# LTC2325.net
KiCad netlist of a schematic drawn in Altium Designer
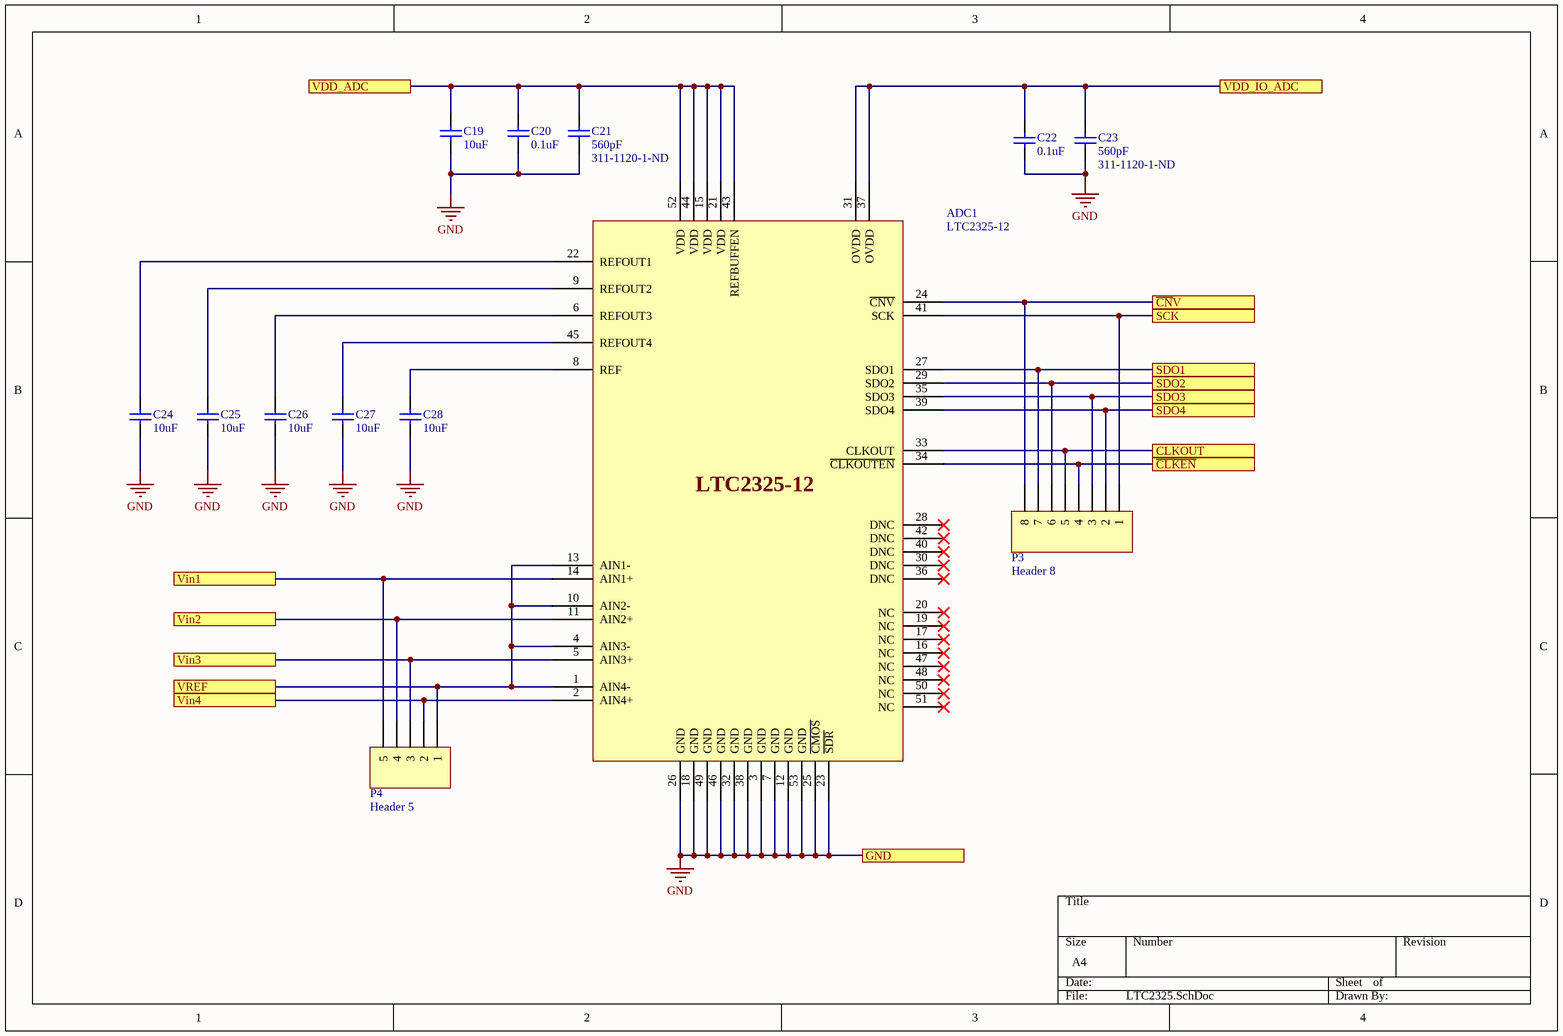
[diagram p0: LTC2325.SchDoc]

(export (version "E")
  (design (tool "Eeschema 10.0.6"))
  (components
    (comp (ref "ADC1")
      (value "LTC2325-12")
      (footprint "LTC2320HUKG")
      (description "Quad, 12-Bit, 5Msps/Ch Simultaneous Sampling ADC")
      (libsource (lib "Chip1_TestBoard") (part "LTC2325-12"))
    )
    (comp (ref "C19")
      (value "10uF")
      (footprint "CLS_Library:C0805")
      (description "Cap 10uF")
      (fields
        (field (name "MANUFACTURER") "Taiyo Yuden")
        (field (name "MANUFACTURER PART NUMBER") "UMK212SD103KD-T")
      )
      (libsource (lib "Chip1_TestBoard") (part "Cap 10uF"))
    )
    (comp (ref "C20")
      (value "0.1uF")
      (footprint "CLS_Library:C0805")
      (description "Cap 0.1uF")
      (fields
        (field (name "MANUFACTURER") "Taiyo Yuden")
        (field (name "MANUFACTURER PART NUMBER") "UMK212SD103KD-T")
      )
      (libsource (lib "Chip1_TestBoard") (part "Cap 0.1uF"))
    )
    (comp (ref "C21")
      (value "560pF")
      (footprint "CLS_Library:C0805")
      (description "Cap 560pF")
      (fields
        (field (name "MANUFACTURER") "Taiyo Yuden")
        (field (name "MANUFACTURER PART NUMBER") "UMK212SD103KD-T")
        (field (name "SUPPLIER PART NUMBER 1") "311-1120-1-ND")
      )
      (libsource (lib "Chip1_TestBoard") (part "Cap 560pF"))
    )
    (comp (ref "C22")
      (value "0.1uF")
      (footprint "CLS_Library:C0805")
      (description "Cap 0.1uF")
      (fields
        (field (name "MANUFACTURER") "Taiyo Yuden")
        (field (name "MANUFACTURER PART NUMBER") "UMK212SD103KD-T")
      )
      (libsource (lib "Chip1_TestBoard") (part "Cap 0.1uF"))
    )
    (comp (ref "C23")
      (value "560pF")
      (footprint "CLS_Library:C0805")
      (description "Cap 560pF")
      (fields
        (field (name "MANUFACTURER") "Taiyo Yuden")
        (field (name "MANUFACTURER PART NUMBER") "UMK212SD103KD-T")
        (field (name "SUPPLIER PART NUMBER 1") "311-1120-1-ND")
      )
      (libsource (lib "Chip1_TestBoard") (part "Cap 560pF"))
    )
    (comp (ref "C24")
      (value "10uF")
      (footprint "CLS_Library:C0805")
      (description "Cap 10uF")
      (fields
        (field (name "MANUFACTURER") "Taiyo Yuden")
        (field (name "MANUFACTURER PART NUMBER") "UMK212SD103KD-T")
      )
      (libsource (lib "Chip1_TestBoard") (part "Cap 10uF"))
    )
    (comp (ref "C25")
      (value "10uF")
      (footprint "CLS_Library:C0805")
      (description "Cap 10uF")
      (fields
        (field (name "MANUFACTURER") "Taiyo Yuden")
        (field (name "MANUFACTURER PART NUMBER") "UMK212SD103KD-T")
      )
      (libsource (lib "Chip1_TestBoard") (part "Cap 10uF"))
    )
    (comp (ref "C26")
      (value "10uF")
      (footprint "CLS_Library:C0805")
      (description "Cap 10uF")
      (fields
        (field (name "MANUFACTURER") "Taiyo Yuden")
        (field (name "MANUFACTURER PART NUMBER") "UMK212SD103KD-T")
      )
      (libsource (lib "Chip1_TestBoard") (part "Cap 10uF"))
    )
    (comp (ref "C27")
      (value "10uF")
      (footprint "CLS_Library:C0805")
      (description "Cap 10uF")
      (fields
        (field (name "MANUFACTURER") "Taiyo Yuden")
        (field (name "MANUFACTURER PART NUMBER") "UMK212SD103KD-T")
      )
      (libsource (lib "Chip1_TestBoard") (part "Cap 10uF"))
    )
    (comp (ref "C28")
      (value "10uF")
      (footprint "CLS_Library:C0805")
      (description "Cap 10uF")
      (fields
        (field (name "MANUFACTURER") "Taiyo Yuden")
        (field (name "MANUFACTURER PART NUMBER") "UMK212SD103KD-T")
      )
      (libsource (lib "Chip1_TestBoard") (part "Cap 10uF"))
    )
    (comp (ref "P3")
      (value "Header 8")
      (footprint "HDR1X8")
      (description "Header, 8-Pin")
      (fields (field (name "PUBLISHER") "Altium Limited"))
      (libsource (lib "Miscellaneous Connectors") (part "Header 8"))
    )
    (comp (ref "P4")
      (value "Header 5")
      (footprint "HDR1X5")
      (description "Header, 5-Pin")
      (fields (field (name "PUBLISHER") "Altium Limited"))
      (libsource (lib "Miscellaneous Connectors") (part "Header 5"))
    )
  )
  (nets
    (net (code "1") (name "/CLKOUT") (class "Default")
      (node (ref "ADC1") (pin "33") (pinfunction "CLKOUT_33") (pintype "passive"))
      (node (ref "P3") (pin "5") (pinfunction "5_5") (pintype "passive"))
    )
    (net (code "2") (name "/SCK") (class "Default")
      (node (ref "ADC1") (pin "41") (pinfunction "SCK_41") (pintype "passive"))
      (node (ref "P3") (pin "1") (pinfunction "1_1") (pintype "passive"))
    )
    (net (code "3") (name "/SDO1") (class "Default")
      (node (ref "ADC1") (pin "27") (pinfunction "SDO1_27") (pintype "passive"))
      (node (ref "P3") (pin "7") (pinfunction "7_7") (pintype "passive"))
    )
    (net (code "4") (name "/SDO2") (class "Default")
      (node (ref "ADC1") (pin "29") (pinfunction "SDO2_29") (pintype "passive"))
      (node (ref "P3") (pin "6") (pinfunction "6_6") (pintype "passive"))
    )
    (net (code "5") (name "/SDO3") (class "Default")
      (node (ref "ADC1") (pin "35") (pinfunction "SDO3_35") (pintype "passive"))
      (node (ref "P3") (pin "3") (pinfunction "3_3") (pintype "passive"))
    )
    (net (code "6") (name "/SDO4") (class "Default")
      (node (ref "ADC1") (pin "39") (pinfunction "SDO4_39") (pintype "passive"))
      (node (ref "P3") (pin "2") (pinfunction "2_2") (pintype "passive"))
    )
    (net (code "7") (name "/VDD_ADC") (class "Default")
      (node (ref "ADC1") (pin "15") (pinfunction "VDD_15") (pintype "passive"))
      (node (ref "ADC1") (pin "21") (pinfunction "VDD_21") (pintype "passive"))
      (node (ref "ADC1") (pin "43") (pinfunction "REFBUFFEN_43") (pintype "passive"))
      (node (ref "ADC1") (pin "44") (pinfunction "VDD_44") (pintype "passive"))
      (node (ref "ADC1") (pin "52") (pinfunction "VDD_52") (pintype "passive"))
      (node (ref "C19") (pin "2") (pinfunction "2_2") (pintype "passive"))
      (node (ref "C20") (pin "2") (pinfunction "2_2") (pintype "passive"))
      (node (ref "C21") (pin "2") (pinfunction "2_2") (pintype "passive"))
    )
    (net (code "8") (name "/VDD_IO_ADC") (class "Default")
      (node (ref "ADC1") (pin "31") (pinfunction "OVDD_31") (pintype "passive"))
      (node (ref "ADC1") (pin "37") (pinfunction "OVDD_37") (pintype "passive"))
      (node (ref "C22") (pin "2") (pinfunction "2_2") (pintype "passive"))
      (node (ref "C23") (pin "2") (pinfunction "2_2") (pintype "passive"))
    )
    (net (code "9") (name "/VREF") (class "Default")
      (node (ref "ADC1") (pin "1") (pinfunction "AIN4-_1") (pintype "passive"))
      (node (ref "ADC1") (pin "10") (pinfunction "AIN2-_10") (pintype "passive"))
      (node (ref "ADC1") (pin "13") (pinfunction "AIN1-_13") (pintype "passive"))
      (node (ref "ADC1") (pin "4") (pinfunction "AIN3-_4") (pintype "passive"))
      (node (ref "P4") (pin "1") (pinfunction "1_1") (pintype "passive"))
    )
    (net (code "10") (name "/Vin1") (class "Default")
      (node (ref "ADC1") (pin "14") (pinfunction "AIN1+_14") (pintype "passive"))
      (node (ref "P4") (pin "5") (pinfunction "5_5") (pintype "passive"))
    )
    (net (code "11") (name "/Vin2") (class "Default")
      (node (ref "ADC1") (pin "11") (pinfunction "AIN2+_11") (pintype "passive"))
      (node (ref "P4") (pin "4") (pinfunction "4_4") (pintype "passive"))
    )
    (net (code "12") (name "/Vin3") (class "Default")
      (node (ref "ADC1") (pin "5") (pinfunction "AIN3+_5") (pintype "passive"))
      (node (ref "P4") (pin "3") (pinfunction "3_3") (pintype "passive"))
    )
    (net (code "13") (name "/Vin4") (class "Default")
      (node (ref "ADC1") (pin "2") (pinfunction "AIN4+_2") (pintype "passive"))
      (node (ref "P4") (pin "2") (pinfunction "2_2") (pintype "passive"))
    )
    (net (code "14") (name "/~{CLKEN}") (class "Default")
      (node (ref "ADC1") (pin "34") (pinfunction "~{CLKOUTEN}_34") (pintype "passive"))
      (node (ref "P3") (pin "4") (pinfunction "4_4") (pintype "passive"))
    )
    (net (code "15") (name "/~{CN}V") (class "Default")
      (node (ref "ADC1") (pin "24") (pinfunction "~{CNV}_24") (pintype "passive"))
      (node (ref "P3") (pin "8") (pinfunction "8_8") (pintype "passive"))
    )
    (net (code "16") (name "GND") (class "Default")
      (node (ref "ADC1") (pin "12") (pinfunction "GND_12") (pintype "passive"))
      (node (ref "ADC1") (pin "18") (pinfunction "GND_18") (pintype "passive"))
      (node (ref "ADC1") (pin "23") (pinfunction "~{SDR}_23") (pintype "passive"))
      (node (ref "ADC1") (pin "25") (pinfunction "~{CMOS}_25") (pintype "passive"))
      (node (ref "ADC1") (pin "26") (pinfunction "GND_26") (pintype "passive"))
      (node (ref "ADC1") (pin "3") (pinfunction "GND_3") (pintype "passive"))
      (node (ref "ADC1") (pin "32") (pinfunction "GND_32") (pintype "passive"))
      (node (ref "ADC1") (pin "38") (pinfunction "GND_38") (pintype "passive"))
      (node (ref "ADC1") (pin "46") (pinfunction "GND_46") (pintype "passive"))
      (node (ref "ADC1") (pin "49") (pinfunction "GND_49") (pintype "passive"))
      (node (ref "ADC1") (pin "53") (pinfunction "GND_53") (pintype "passive"))
      (node (ref "ADC1") (pin "7") (pinfunction "GND_7") (pintype "passive"))
      (node (ref "C19") (pin "1") (pinfunction "1_1") (pintype "passive"))
      (node (ref "C20") (pin "1") (pinfunction "1_1") (pintype "passive"))
      (node (ref "C21") (pin "1") (pinfunction "1_1") (pintype "passive"))
      (node (ref "C22") (pin "1") (pinfunction "1_1") (pintype "passive"))
      (node (ref "C23") (pin "1") (pinfunction "1_1") (pintype "passive"))
      (node (ref "C24") (pin "1") (pinfunction "1_1") (pintype "passive"))
      (node (ref "C25") (pin "1") (pinfunction "1_1") (pintype "passive"))
      (node (ref "C26") (pin "1") (pinfunction "1_1") (pintype "passive"))
      (node (ref "C27") (pin "1") (pinfunction "1_1") (pintype "passive"))
      (node (ref "C28") (pin "1") (pinfunction "1_1") (pintype "passive"))
    )
    (net (code "17") (name "Net-(ADC1-REF)") (class "Default")
      (node (ref "ADC1") (pin "8") (pinfunction "REF_8") (pintype "passive"))
      (node (ref "C28") (pin "2") (pinfunction "2_2") (pintype "passive"))
    )
    (net (code "18") (name "Net-(ADC1-REFOUT1)") (class "Default")
      (node (ref "ADC1") (pin "22") (pinfunction "REFOUT1_22") (pintype "passive"))
      (node (ref "C24") (pin "2") (pinfunction "2_2") (pintype "passive"))
    )
    (net (code "19") (name "Net-(ADC1-REFOUT2)") (class "Default")
      (node (ref "ADC1") (pin "9") (pinfunction "REFOUT2_9") (pintype "passive"))
      (node (ref "C25") (pin "2") (pinfunction "2_2") (pintype "passive"))
    )
    (net (code "20") (name "Net-(ADC1-REFOUT3)") (class "Default")
      (node (ref "ADC1") (pin "6") (pinfunction "REFOUT3_6") (pintype "passive"))
      (node (ref "C26") (pin "2") (pinfunction "2_2") (pintype "passive"))
    )
    (net (code "21") (name "Net-(ADC1-REFOUT4)") (class "Default")
      (node (ref "ADC1") (pin "45") (pinfunction "REFOUT4_45") (pintype "passive"))
      (node (ref "C27") (pin "2") (pinfunction "2_2") (pintype "passive"))
    )
    (net (code "22") (name "unconnected-(ADC1-DNC-Pad28)") (class "Default")
      (node (ref "ADC1") (pin "28") (pinfunction "DNC_28") (pintype "passive+no_connect"))
    )
    (net (code "23") (name "unconnected-(ADC1-DNC-Pad30)") (class "Default")
      (node (ref "ADC1") (pin "30") (pinfunction "DNC_30") (pintype "passive+no_connect"))
    )
    (net (code "24") (name "unconnected-(ADC1-DNC-Pad36)") (class "Default")
      (node (ref "ADC1") (pin "36") (pinfunction "DNC_36") (pintype "passive+no_connect"))
    )
    (net (code "25") (name "unconnected-(ADC1-DNC-Pad40)") (class "Default")
      (node (ref "ADC1") (pin "40") (pinfunction "DNC_40") (pintype "passive+no_connect"))
    )
    (net (code "26") (name "unconnected-(ADC1-DNC-Pad42)") (class "Default")
      (node (ref "ADC1") (pin "42") (pinfunction "DNC_42") (pintype "passive+no_connect"))
    )
    (net (code "27") (name "unconnected-(ADC1-NC-Pad16)") (class "Default")
      (node (ref "ADC1") (pin "16") (pinfunction "NC_16") (pintype "passive+no_connect"))
    )
    (net (code "28") (name "unconnected-(ADC1-NC-Pad17)") (class "Default")
      (node (ref "ADC1") (pin "17") (pinfunction "NC_17") (pintype "passive+no_connect"))
    )
    (net (code "29") (name "unconnected-(ADC1-NC-Pad19)") (class "Default")
      (node (ref "ADC1") (pin "19") (pinfunction "NC_19") (pintype "passive+no_connect"))
    )
    (net (code "30") (name "unconnected-(ADC1-NC-Pad20)") (class "Default")
      (node (ref "ADC1") (pin "20") (pinfunction "NC_20") (pintype "passive+no_connect"))
    )
    (net (code "31") (name "unconnected-(ADC1-NC-Pad47)") (class "Default")
      (node (ref "ADC1") (pin "47") (pinfunction "NC_47") (pintype "passive+no_connect"))
    )
    (net (code "32") (name "unconnected-(ADC1-NC-Pad48)") (class "Default")
      (node (ref "ADC1") (pin "48") (pinfunction "NC_48") (pintype "passive+no_connect"))
    )
    (net (code "33") (name "unconnected-(ADC1-NC-Pad50)") (class "Default")
      (node (ref "ADC1") (pin "50") (pinfunction "NC_50") (pintype "passive+no_connect"))
    )
    (net (code "34") (name "unconnected-(ADC1-NC-Pad51)") (class "Default")
      (node (ref "ADC1") (pin "51") (pinfunction "NC_51") (pintype "passive+no_connect"))
    )
  )
)
